# BMP280_breakout.net
KiCad netlist of a schematic drawn in EAGLE
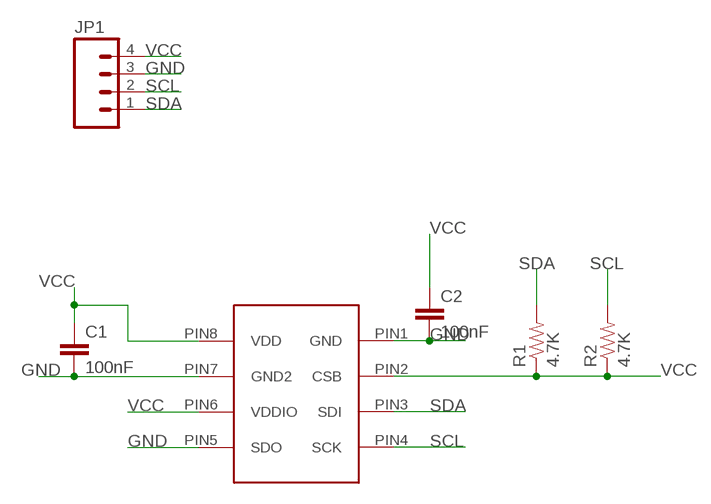
[diagram p0: schematic, sheet 1]

(export (version "E")
  (design (tool "Eeschema 10.0.6"))
  (components
    (comp (ref "C1")
      (value "100nF")
      (footprint "eagle-import:0603-CAP")
      (libsource (lib "eagle-import") (part "CAP0603-CAP"))
    )
    (comp (ref "C2")
      (value "100nF")
      (footprint "eagle-import:0603-CAP")
      (libsource (lib "eagle-import") (part "CAP0603-CAP"))
    )
    (comp (ref "JP1")
      (value "M04PTH")
      (footprint "eagle-import:1X04")
      (libsource (lib "eagle-import") (part "M04PTH"))
    )
    (comp (ref "R1")
      (value "4.7K")
      (footprint "eagle-import:0603-RES")
      (libsource (lib "eagle-import") (part "RESISTOR0603"))
    )
    (comp (ref "R2")
      (value "4.7K")
      (footprint "eagle-import:0603-RES")
      (libsource (lib "eagle-import") (part "RESISTOR0603"))
    )
    (comp (ref "U$1")
      (value "BMP280")
      (footprint "eagle-import:BMP280")
      (libsource (lib "eagle-import") (part "BMP280"))
    )
  )
  (nets
    (net (code "1") (name "/GND") (class "Default")
      (node (ref "C1") (pin "2") (pinfunction "2_2") (pintype "passive"))
      (node (ref "C2") (pin "2") (pinfunction "2_2") (pintype "passive"))
      (node (ref "JP1") (pin "3") (pinfunction "3_3") (pintype "passive"))
      (node (ref "U$1") (pin "PIN1") (pinfunction "GND_PIN1") (pintype "bidirectional"))
      (node (ref "U$1") (pin "PIN5") (pinfunction "SDO_PIN5") (pintype "bidirectional"))
      (node (ref "U$1") (pin "PIN7") (pinfunction "GND2_PIN7") (pintype "bidirectional"))
    )
    (net (code "2") (name "/SCL") (class "Default")
      (node (ref "JP1") (pin "2") (pinfunction "2_2") (pintype "passive"))
      (node (ref "R2") (pin "2") (pinfunction "2_2") (pintype "passive"))
      (node (ref "U$1") (pin "PIN4") (pinfunction "SCK_PIN4") (pintype "bidirectional"))
    )
    (net (code "3") (name "/SDA") (class "Default")
      (node (ref "JP1") (pin "1") (pinfunction "1_1") (pintype "passive"))
      (node (ref "R1") (pin "2") (pinfunction "2_2") (pintype "passive"))
      (node (ref "U$1") (pin "PIN3") (pinfunction "SDI_PIN3") (pintype "bidirectional"))
    )
    (net (code "4") (name "/VCC") (class "Default")
      (node (ref "C1") (pin "1") (pinfunction "1_1") (pintype "passive"))
      (node (ref "C2") (pin "1") (pinfunction "1_1") (pintype "passive"))
      (node (ref "JP1") (pin "4") (pinfunction "4_4") (pintype "passive"))
      (node (ref "R1") (pin "1") (pinfunction "1_1") (pintype "passive"))
      (node (ref "R2") (pin "1") (pinfunction "1_1") (pintype "passive"))
      (node (ref "U$1") (pin "PIN2") (pinfunction "CSB_PIN2") (pintype "bidirectional"))
      (node (ref "U$1") (pin "PIN6") (pinfunction "VDDIO_PIN6") (pintype "bidirectional"))
      (node (ref "U$1") (pin "PIN8") (pinfunction "VDD_PIN8") (pintype "bidirectional"))
    )
  )
)
